# DualMotorCape-v1.net
KiCad netlist of a schematic drawn in EAGLE
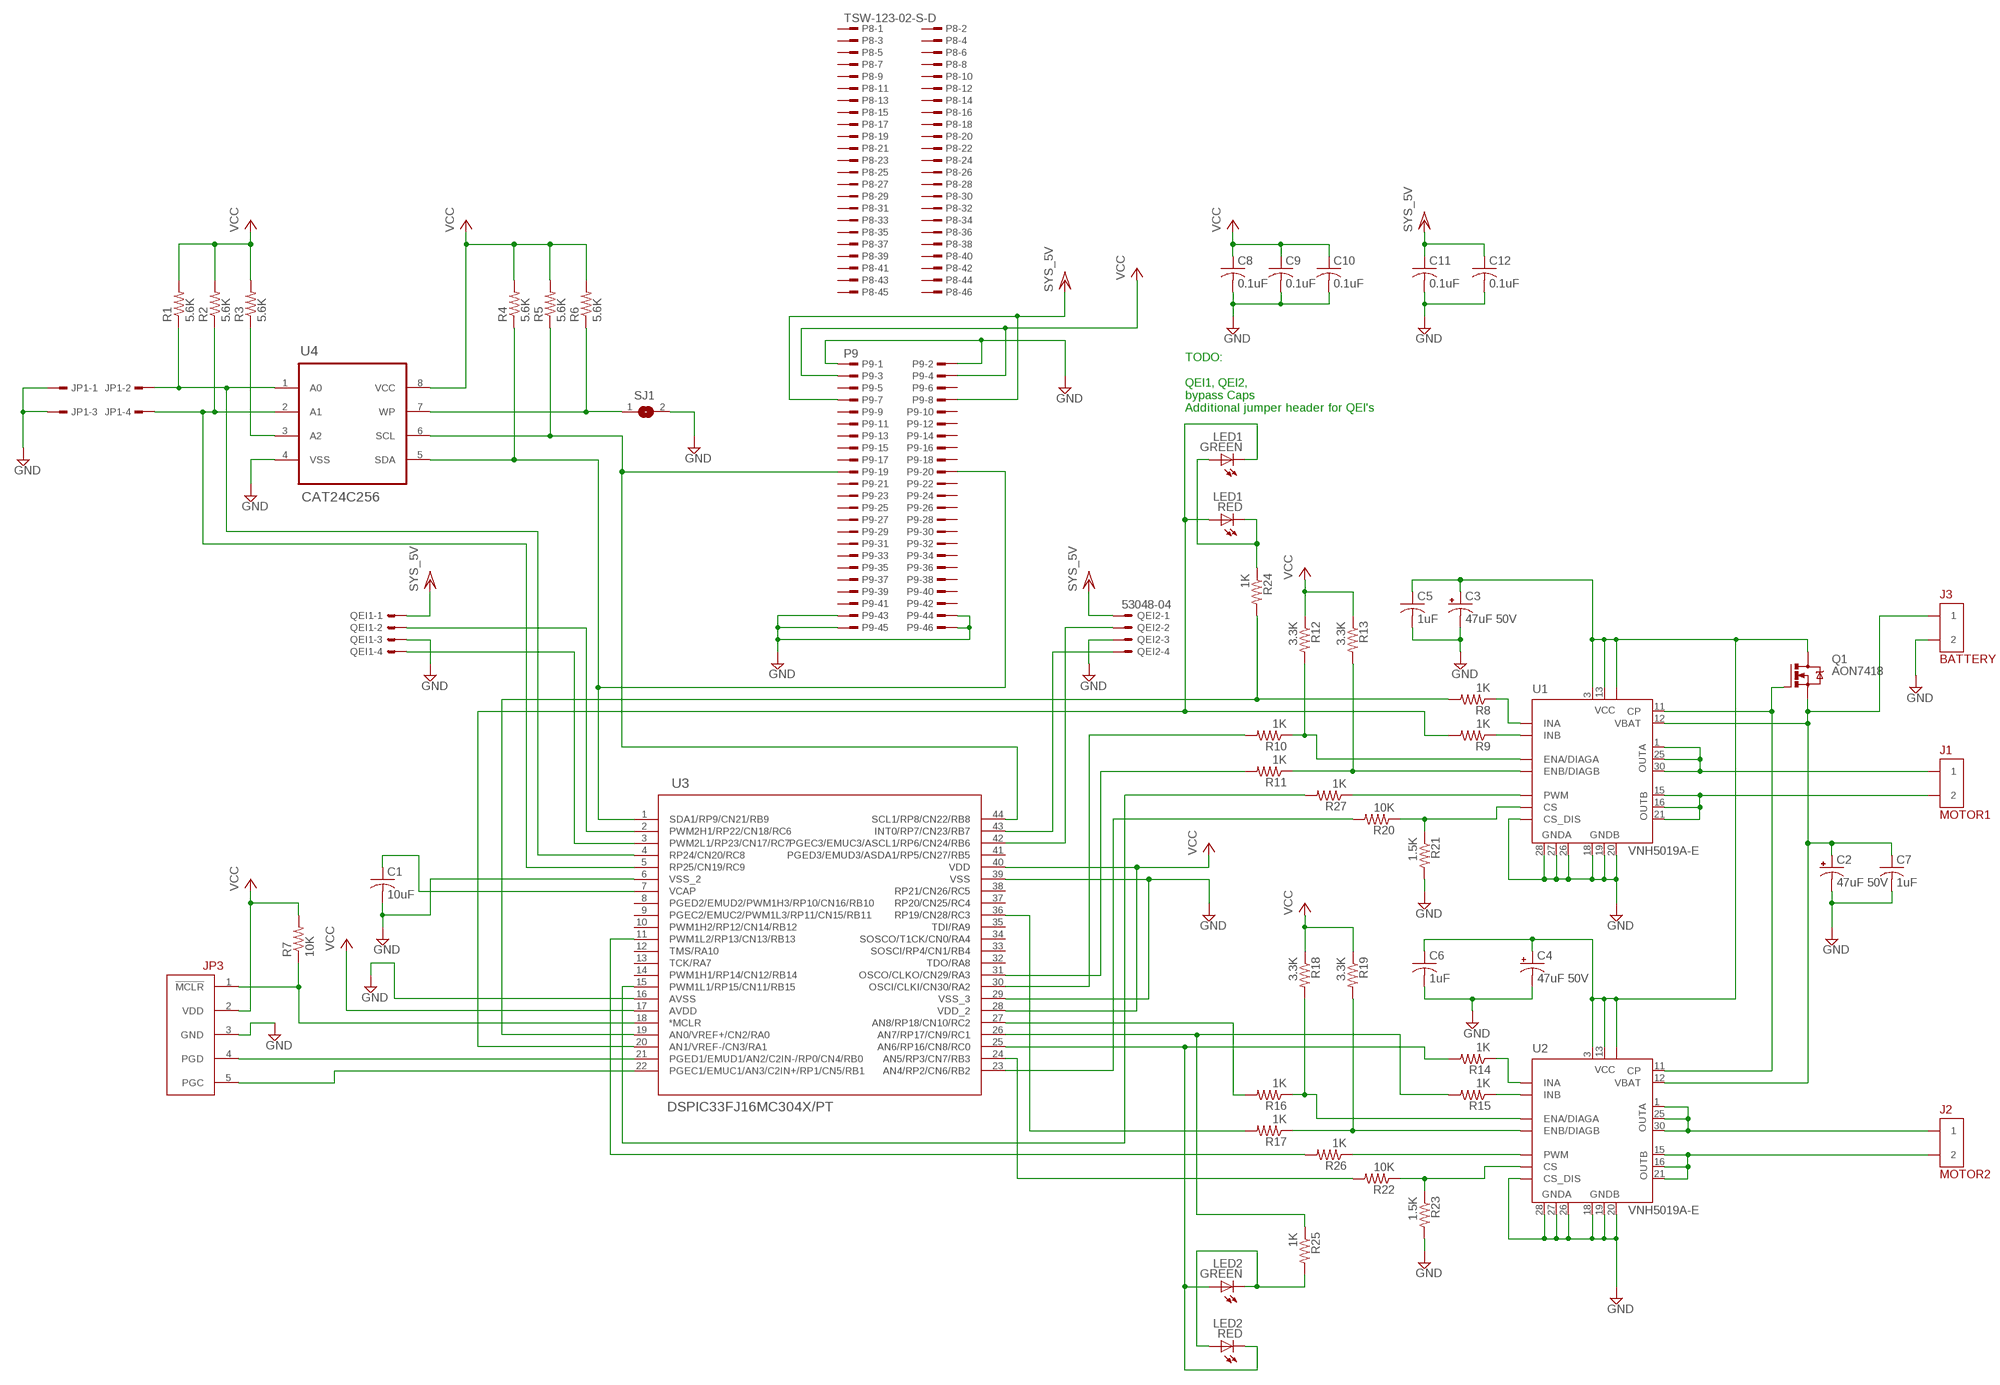
[diagram p0: schematic, sheet 1]

(export (version "E")
  (design (tool "Eeschema 10.0.6"))
  (components
    (comp (ref "C1")
      (value "10uF")
      (footprint "eagle-import:C0805")
      (libsource (lib "eagle-import") (part "C-USC0805"))
    )
    (comp (ref "C2")
      (value "47uF 50V")
      (footprint "eagle-import:UD-6,3X7,7_NICHICON")
      (libsource (lib "eagle-import") (part "CPOL-USUD-6,3X7,7"))
    )
    (comp (ref "C3")
      (value "47uF 50V")
      (footprint "eagle-import:UD-6,3X7,7_NICHICON")
      (libsource (lib "eagle-import") (part "CPOL-USUD-6,3X7,7"))
    )
    (comp (ref "C4")
      (value "47uF 50V")
      (footprint "eagle-import:UD-6,3X7,7_NICHICON")
      (libsource (lib "eagle-import") (part "CPOL-USUD-6,3X7,7"))
    )
    (comp (ref "C5")
      (value "1uF")
      (footprint "eagle-import:C0603")
      (libsource (lib "eagle-import") (part "C-USC0603"))
    )
    (comp (ref "C6")
      (value "1uF")
      (footprint "eagle-import:C0603")
      (libsource (lib "eagle-import") (part "C-USC0603"))
    )
    (comp (ref "C7")
      (value "1uF")
      (footprint "eagle-import:C0603")
      (libsource (lib "eagle-import") (part "C-USC0603"))
    )
    (comp (ref "C8")
      (value "0.1uF")
      (footprint "eagle-import:C0603")
      (libsource (lib "eagle-import") (part "C-USC0603"))
    )
    (comp (ref "C9")
      (value "0.1uF")
      (footprint "eagle-import:C0603")
      (libsource (lib "eagle-import") (part "C-USC0603"))
    )
    (comp (ref "C10")
      (value "0.1uF")
      (footprint "eagle-import:C0603")
      (libsource (lib "eagle-import") (part "C-USC0603"))
    )
    (comp (ref "C11")
      (value "0.1uF")
      (footprint "eagle-import:C0603")
      (libsource (lib "eagle-import") (part "C-USC0603"))
    )
    (comp (ref "C12")
      (value "0.1uF")
      (footprint "eagle-import:C0603")
      (libsource (lib "eagle-import") (part "C-USC0603"))
    )
    (comp (ref "J1")
      (value "MOTOR1")
      (footprint "eagle-import:TERMINAL-BLOCK-2.54MM-2")
      (libsource (lib "eagle-import") (part "TERMINAL-BLOCK-2"))
    )
    (comp (ref "J2")
      (value "MOTOR2")
      (footprint "eagle-import:TERMINAL-BLOCK-2.54MM-2")
      (libsource (lib "eagle-import") (part "TERMINAL-BLOCK-2"))
    )
    (comp (ref "J3")
      (value "BATTERY")
      (footprint "eagle-import:TERMINAL-BLOCK-2.54MM-2")
      (libsource (lib "eagle-import") (part "TERMINAL-BLOCK-2"))
    )
    (comp (ref "JP1")
      (value "TSW-102-02-S-D")
      (footprint "eagle-import:TSW-102-02-S-D")
      (libsource (lib "eagle-import") (part "TSW-102-02-S-D"))
    )
    (comp (ref "JP3")
      (value "ICD2/3-HEADER")
      (footprint "eagle-import:ICD2_3-HEADER")
      (libsource (lib "eagle-import") (part "ICD2/3-HEADER"))
    )
    (comp (ref "LED1")
      (value "KINGBRIGHT-BI-COLOR-LED")
      (footprint "eagle-import:LED-1.6X1.5MM-BI-COLOR")
      (libsource (lib "eagle-import") (part "KINGBRIGHT-BI-COLOR-LED"))
    )
    (comp (ref "LED2")
      (value "KINGBRIGHT-BI-COLOR-LED")
      (footprint "eagle-import:LED-1.6X1.5MM-BI-COLOR")
      (libsource (lib "eagle-import") (part "KINGBRIGHT-BI-COLOR-LED"))
    )
    (comp (ref "P8")
      (value "TSW-123-02-S-D")
      (footprint "eagle-import:TSW-123-02-S-D")
      (libsource (lib "eagle-import") (part "TSW-123-02-S-D"))
    )
    (comp (ref "P9")
      (value "P9")
      (footprint "eagle-import:TSW-123-02-S-D")
      (libsource (lib "eagle-import") (part "TSW-123-02-S-D"))
    )
    (comp (ref "Q1")
      (value "AON7418")
      (footprint "eagle-import:DFN3.3X3.3")
      (libsource (lib "eagle-import") (part "MOSFET-N"))
    )
    (comp (ref "QEI1")
      (value "53048-04")
      (footprint "eagle-import:53048-04")
      (fields (field (name "MF") "MOLEX") (field (name "MPN") "53048-0410"))
      (libsource (lib "eagle-import") (part "53?-04048"))
    )
    (comp (ref "QEI2")
      (value "53048-04")
      (footprint "eagle-import:53048-04")
      (fields (field (name "MF") "MOLEX") (field (name "MPN") "53048-0410"))
      (libsource (lib "eagle-import") (part "53?-04048"))
    )
    (comp (ref "R1")
      (value "5.6K")
      (footprint "eagle-import:R0603")
      (libsource (lib "eagle-import") (part "R-US_R0603"))
    )
    (comp (ref "R2")
      (value "5.6K")
      (footprint "eagle-import:R0603")
      (libsource (lib "eagle-import") (part "R-US_R0603"))
    )
    (comp (ref "R3")
      (value "5.6K")
      (footprint "eagle-import:R0603")
      (libsource (lib "eagle-import") (part "R-US_R0603"))
    )
    (comp (ref "R4")
      (value "5.6K")
      (footprint "eagle-import:R0603")
      (libsource (lib "eagle-import") (part "R-US_R0603"))
    )
    (comp (ref "R5")
      (value "5.6K")
      (footprint "eagle-import:R0603")
      (libsource (lib "eagle-import") (part "R-US_R0603"))
    )
    (comp (ref "R6")
      (value "5.6K")
      (footprint "eagle-import:R0603")
      (libsource (lib "eagle-import") (part "R-US_R0603"))
    )
    (comp (ref "R7")
      (value "10K")
      (footprint "eagle-import:R0603")
      (libsource (lib "eagle-import") (part "R-US_R0603"))
    )
    (comp (ref "R8")
      (value "1K")
      (footprint "eagle-import:R0603")
      (libsource (lib "eagle-import") (part "R-US_R0603"))
    )
    (comp (ref "R9")
      (value "1K")
      (footprint "eagle-import:R0603")
      (libsource (lib "eagle-import") (part "R-US_R0603"))
    )
    (comp (ref "R10")
      (value "1K")
      (footprint "eagle-import:R0603")
      (libsource (lib "eagle-import") (part "R-US_R0603"))
    )
    (comp (ref "R11")
      (value "1K")
      (footprint "eagle-import:R0603")
      (libsource (lib "eagle-import") (part "R-US_R0603"))
    )
    (comp (ref "R12")
      (value "3.3K")
      (footprint "eagle-import:R0603")
      (libsource (lib "eagle-import") (part "R-US_R0603"))
    )
    (comp (ref "R13")
      (value "3.3K")
      (footprint "eagle-import:R0603")
      (libsource (lib "eagle-import") (part "R-US_R0603"))
    )
    (comp (ref "R14")
      (value "1K")
      (footprint "eagle-import:R0603")
      (libsource (lib "eagle-import") (part "R-US_R0603"))
    )
    (comp (ref "R15")
      (value "1K")
      (footprint "eagle-import:R0603")
      (libsource (lib "eagle-import") (part "R-US_R0603"))
    )
    (comp (ref "R16")
      (value "1K")
      (footprint "eagle-import:R0603")
      (libsource (lib "eagle-import") (part "R-US_R0603"))
    )
    (comp (ref "R17")
      (value "1K")
      (footprint "eagle-import:R0603")
      (libsource (lib "eagle-import") (part "R-US_R0603"))
    )
    (comp (ref "R18")
      (value "3.3K")
      (footprint "eagle-import:R0603")
      (libsource (lib "eagle-import") (part "R-US_R0603"))
    )
    (comp (ref "R19")
      (value "3.3K")
      (footprint "eagle-import:R0603")
      (libsource (lib "eagle-import") (part "R-US_R0603"))
    )
    (comp (ref "R20")
      (value "10K")
      (footprint "eagle-import:R0603")
      (libsource (lib "eagle-import") (part "R-US_R0603"))
    )
    (comp (ref "R21")
      (value "1.5K")
      (footprint "eagle-import:R0603")
      (libsource (lib "eagle-import") (part "R-US_R0603"))
    )
    (comp (ref "R22")
      (value "10K")
      (footprint "eagle-import:R0603")
      (libsource (lib "eagle-import") (part "R-US_R0603"))
    )
    (comp (ref "R23")
      (value "1.5K")
      (footprint "eagle-import:R0603")
      (libsource (lib "eagle-import") (part "R-US_R0603"))
    )
    (comp (ref "R24")
      (value "1K")
      (footprint "eagle-import:R0603")
      (libsource (lib "eagle-import") (part "R-US_R0603"))
    )
    (comp (ref "R25")
      (value "1K")
      (footprint "eagle-import:R0603")
      (libsource (lib "eagle-import") (part "R-US_R0603"))
    )
    (comp (ref "R26")
      (value "1K")
      (footprint "eagle-import:R0603")
      (libsource (lib "eagle-import") (part "R-US_R0603"))
    )
    (comp (ref "R27")
      (value "1K")
      (footprint "eagle-import:R0603")
      (libsource (lib "eagle-import") (part "R-US_R0603"))
    )
    (comp (ref "SJ1") (value "SJ") (footprint "eagle-import:SJ") (libsource (lib "eagle-import") (part "SJ")))
    (comp (ref "U1")
      (value "VNH5019A-E")
      (footprint "eagle-import:VNH5019A-E")
      (libsource (lib "eagle-import") (part "VNH5019A-E"))
    )
    (comp (ref "U2")
      (value "VNH5019A-E")
      (footprint "eagle-import:VNH5019A-E")
      (libsource (lib "eagle-import") (part "VNH5019A-E"))
    )
    (comp (ref "U3")
      (value "DSPIC33FJ16MC304X/PT")
      (footprint "eagle-import:TQFP44_MC")
      (libsource (lib "eagle-import") (part "DSPIC33FJ16MC304X/PT"))
    )
    (comp (ref "U4")
      (value "CAT24C256")
      (footprint "eagle-import:SOIC-8")
      (libsource (lib "eagle-import") (part "CAT24C256"))
    )
  )
  (nets
    (net (code "1") (name "GND") (class "Default")
      (node (ref "C1") (pin "2") (pinfunction "2_2") (pintype "passive"))
      (node (ref "C10") (pin "2") (pinfunction "2_2") (pintype "passive"))
      (node (ref "C11") (pin "2") (pinfunction "2_2") (pintype "passive"))
      (node (ref "C12") (pin "2") (pinfunction "2_2") (pintype "passive"))
      (node (ref "C2") (pin "-") (pinfunction "-_-") (pintype "passive"))
      (node (ref "C3") (pin "-") (pinfunction "-_-") (pintype "passive"))
      (node (ref "C4") (pin "-") (pinfunction "-_-") (pintype "passive"))
      (node (ref "C5") (pin "2") (pinfunction "2_2") (pintype "passive"))
      (node (ref "C6") (pin "2") (pinfunction "2_2") (pintype "passive"))
      (node (ref "C7") (pin "2") (pinfunction "2_2") (pintype "passive"))
      (node (ref "C8") (pin "2") (pinfunction "2_2") (pintype "passive"))
      (node (ref "C9") (pin "2") (pinfunction "2_2") (pintype "passive"))
      (node (ref "J3") (pin "2") (pinfunction "2_2") (pintype "passive"))
      (node (ref "JP1") (pin "1") (pinfunction "1_1") (pintype "passive"))
      (node (ref "JP1") (pin "3") (pinfunction "1_3") (pintype "passive"))
      (node (ref "JP3") (pin "3") (pinfunction "GND_3") (pintype "bidirectional"))
      (node (ref "P9") (pin "1") (pinfunction "1_1") (pintype "passive"))
      (node (ref "P9") (pin "2") (pinfunction "1_2") (pintype "passive"))
      (node (ref "P9") (pin "43") (pinfunction "1_43") (pintype "passive"))
      (node (ref "P9") (pin "44") (pinfunction "1_44") (pintype "passive"))
      (node (ref "P9") (pin "45") (pinfunction "1_45") (pintype "passive"))
      (node (ref "P9") (pin "46") (pinfunction "1_46") (pintype "passive"))
      (node (ref "QEI1") (pin "3") (pinfunction "S_3") (pintype "passive"))
      (node (ref "QEI2") (pin "3") (pinfunction "S_3") (pintype "passive"))
      (node (ref "R21") (pin "2") (pinfunction "2_2") (pintype "passive"))
      (node (ref "R23") (pin "2") (pinfunction "2_2") (pintype "passive"))
      (node (ref "SJ1") (pin "2") (pinfunction "2_2") (pintype "passive"))
      (node (ref "U1") (pin "18") (pinfunction "GNDB_18") (pintype "power_in"))
      (node (ref "U1") (pin "19") (pinfunction "GNDB_19") (pintype "power_in"))
      (node (ref "U1") (pin "20") (pinfunction "GNDB_20") (pintype "power_in"))
      (node (ref "U1") (pin "26") (pinfunction "GNDA_26") (pintype "power_in"))
      (node (ref "U1") (pin "27") (pinfunction "GNDA_27") (pintype "power_in"))
      (node (ref "U1") (pin "28") (pinfunction "GNDA_28") (pintype "power_in"))
      (node (ref "U1") (pin "6") (pinfunction "CS_DIS_6") (pintype "input"))
      (node (ref "U2") (pin "18") (pinfunction "GNDB_18") (pintype "power_in"))
      (node (ref "U2") (pin "19") (pinfunction "GNDB_19") (pintype "power_in"))
      (node (ref "U2") (pin "20") (pinfunction "GNDB_20") (pintype "power_in"))
      (node (ref "U2") (pin "26") (pinfunction "GNDA_26") (pintype "power_in"))
      (node (ref "U2") (pin "27") (pinfunction "GNDA_27") (pintype "power_in"))
      (node (ref "U2") (pin "28") (pinfunction "GNDA_28") (pintype "power_in"))
      (node (ref "U2") (pin "6") (pinfunction "CS_DIS_6") (pintype "input"))
      (node (ref "U3") (pin "16") (pinfunction "AVSS_16") (pintype "passive"))
      (node (ref "U3") (pin "29") (pinfunction "VSS_3_29") (pintype "passive"))
      (node (ref "U3") (pin "39") (pinfunction "VSS_39") (pintype "passive"))
      (node (ref "U3") (pin "6") (pinfunction "VSS_2_6") (pintype "passive"))
      (node (ref "U4") (pin "4") (pinfunction "VSS_4") (pintype "power_in"))
    )
    (net (code "2") (name "Net-(C3-Pad+)") (class "Default")
      (node (ref "C3") (pin "+") (pinfunction "+_+") (pintype "passive"))
      (node (ref "C4") (pin "+") (pinfunction "+_+") (pintype "passive"))
      (node (ref "C5") (pin "1") (pinfunction "1_1") (pintype "passive"))
      (node (ref "C6") (pin "1") (pinfunction "1_1") (pintype "passive"))
      (node (ref "Q1") (pin "5") (pinfunction "D_5") (pintype "passive"))
      (node (ref "Q1") (pin "6") (pinfunction "D_6") (pintype "passive"))
      (node (ref "Q1") (pin "7") (pinfunction "D_7") (pintype "passive"))
      (node (ref "Q1") (pin "8") (pinfunction "D_8") (pintype "passive"))
      (node (ref "U1") (pin "13") (pinfunction "VCC_13") (pintype "power_in"))
      (node (ref "U1") (pin "23") (pinfunction "VCC_23") (pintype "power_in"))
      (node (ref "U1") (pin "3") (pinfunction "VCC_3") (pintype "power_in"))
      (node (ref "U2") (pin "13") (pinfunction "VCC_13") (pintype "power_in"))
      (node (ref "U2") (pin "23") (pinfunction "VCC_23") (pintype "power_in"))
      (node (ref "U2") (pin "3") (pinfunction "VCC_3") (pintype "power_in"))
    )
    (net (code "3") (name "Net-(J1-Pad1)") (class "Default")
      (node (ref "J1") (pin "1") (pinfunction "1_1") (pintype "passive"))
      (node (ref "U1") (pin "1") (pinfunction "OUTA_1") (pintype "output"))
      (node (ref "U1") (pin "25") (pinfunction "OUTA_25") (pintype "passive"))
      (node (ref "U1") (pin "30") (pinfunction "OUTA_30") (pintype "passive"))
    )
    (net (code "4") (name "Net-(J1-Pad2)") (class "Default")
      (node (ref "J1") (pin "2") (pinfunction "2_2") (pintype "passive"))
      (node (ref "U1") (pin "15") (pinfunction "OUTB_15") (pintype "output"))
      (node (ref "U1") (pin "16") (pinfunction "OUTB_16") (pintype "passive"))
      (node (ref "U1") (pin "21") (pinfunction "OUTB_21") (pintype "passive"))
    )
    (net (code "5") (name "Net-(J2-Pad1)") (class "Default")
      (node (ref "J2") (pin "1") (pinfunction "1_1") (pintype "passive"))
      (node (ref "U2") (pin "1") (pinfunction "OUTA_1") (pintype "output"))
      (node (ref "U2") (pin "25") (pinfunction "OUTA_25") (pintype "passive"))
      (node (ref "U2") (pin "30") (pinfunction "OUTA_30") (pintype "passive"))
    )
    (net (code "6") (name "Net-(J2-Pad2)") (class "Default")
      (node (ref "J2") (pin "2") (pinfunction "2_2") (pintype "passive"))
      (node (ref "U2") (pin "15") (pinfunction "OUTB_15") (pintype "output"))
      (node (ref "U2") (pin "16") (pinfunction "OUTB_16") (pintype "passive"))
      (node (ref "U2") (pin "21") (pinfunction "OUTB_21") (pintype "passive"))
    )
    (net (code "7") (name "Net-(JP1B-1)") (class "Default")
      (node (ref "JP1") (pin "2") (pinfunction "1_2") (pintype "passive"))
      (node (ref "R1") (pin "1") (pinfunction "1_1") (pintype "passive"))
      (node (ref "U3") (pin "4") (pinfunction "RP24/CN20/RC8_4") (pintype "passive"))
      (node (ref "U4") (pin "1") (pinfunction "A0_1") (pintype "input"))
    )
    (net (code "8") (name "Net-(JP1D-1)") (class "Default")
      (node (ref "JP1") (pin "4") (pinfunction "1_4") (pintype "passive"))
      (node (ref "R2") (pin "1") (pinfunction "1_1") (pintype "passive"))
      (node (ref "U3") (pin "5") (pinfunction "RP25/CN19/RC9_5") (pintype "passive"))
      (node (ref "U4") (pin "2") (pinfunction "A1_2") (pintype "input"))
    )
    (net (code "9") (name "Net-(JP3-PGC)") (class "Default")
      (node (ref "JP3") (pin "5") (pinfunction "PGC_5") (pintype "bidirectional"))
      (node (ref "U3") (pin "22") (pinfunction "PGEC1/EMUC1/AN3/C2IN+/RP1/CN5/RB1_22") (pintype "passive"))
    )
    (net (code "10") (name "Net-(JP3-PGD)") (class "Default")
      (node (ref "JP3") (pin "4") (pinfunction "PGD_4") (pintype "bidirectional"))
      (node (ref "U3") (pin "21") (pinfunction "PGED1/EMUD1/AN2/C2IN-/RP0/CN4/RB0_21") (pintype "passive"))
    )
    (net (code "11") (name "Net-(JP3-~{MCLR})") (class "Default")
      (node (ref "JP3") (pin "1") (pinfunction "~{MCLR}_1") (pintype "bidirectional"))
      (node (ref "R7") (pin "1") (pinfunction "1_1") (pintype "passive"))
      (node (ref "U3") (pin "18") (pinfunction "*MCLR_18") (pintype "passive"))
    )
    (net (code "12") (name "Net-(LED1-Pad2)") (class "Default")
      (node (ref "LED1") (pin "2") (pinfunction "2_2") (pintype "passive"))
      (node (ref "LED1") (pin "3") (pinfunction "3_3") (pintype "passive"))
      (node (ref "R24") (pin "1") (pinfunction "1_1") (pintype "passive"))
    )
    (net (code "13") (name "Net-(LED2-Pad1)") (class "Default")
      (node (ref "LED2") (pin "1") (pinfunction "1_1") (pintype "passive"))
      (node (ref "LED2") (pin "4") (pinfunction "4_4") (pintype "passive"))
      (node (ref "R25") (pin "2") (pinfunction "2_2") (pintype "passive"))
    )
    (net (code "14") (name "Net-(P9K-1)") (class "Default")
      (node (ref "P9") (pin "19") (pinfunction "1_19") (pintype "passive"))
      (node (ref "R5") (pin "1") (pinfunction "1_1") (pintype "passive"))
      (node (ref "U3") (pin "44") (pinfunction "SCL1/RP8/CN22/RB8_44") (pintype "passive"))
      (node (ref "U4") (pin "6") (pinfunction "SCL_6") (pintype "input"))
    )
    (net (code "15") (name "Net-(P9M-1)") (class "Default")
      (node (ref "P9") (pin "20") (pinfunction "1_20") (pintype "passive"))
      (node (ref "R4") (pin "1") (pinfunction "1_1") (pintype "passive"))
      (node (ref "U3") (pin "1") (pinfunction "SDA1/RP9/CN21/RB9_1") (pintype "passive"))
      (node (ref "U4") (pin "5") (pinfunction "SDA_5") (pintype "bidirectional"))
    )
    (net (code "16") (name "Net-(Q1-G)") (class "Default")
      (node (ref "Q1") (pin "4") (pinfunction "G_4") (pintype "passive"))
      (node (ref "U1") (pin "11") (pinfunction "CP_11") (pintype "output"))
      (node (ref "U2") (pin "11") (pinfunction "CP_11") (pintype "output"))
    )
    (net (code "17") (name "Net-(QEI1B-S)") (class "Default")
      (node (ref "QEI1") (pin "2") (pinfunction "S_2") (pintype "passive"))
      (node (ref "U3") (pin "2") (pinfunction "PWM2H1/RP22/CN18/RC6_2") (pintype "passive"))
    )
    (net (code "18") (name "Net-(QEI1D-S)") (class "Default")
      (node (ref "QEI1") (pin "4") (pinfunction "S_4") (pintype "passive"))
      (node (ref "U3") (pin "3") (pinfunction "PWM2L1/RP23/CN17/RC7_3") (pintype "passive"))
    )
    (net (code "19") (name "Net-(QEI2B-S)") (class "Default")
      (node (ref "QEI2") (pin "2") (pinfunction "S_2") (pintype "passive"))
      (node (ref "U3") (pin "42") (pinfunction "PGEC3/EMUC3/ASCL1/RP6/CN24/RB6_42") (pintype "passive"))
    )
    (net (code "20") (name "Net-(QEI2D-S)") (class "Default")
      (node (ref "QEI2") (pin "4") (pinfunction "S_4") (pintype "passive"))
      (node (ref "U3") (pin "43") (pinfunction "INT0/RP7/CN23/RB7_43") (pintype "passive"))
    )
    (net (code "21") (name "Net-(U1-CS)") (class "Default")
      (node (ref "R20") (pin "1") (pinfunction "1_1") (pintype "passive"))
      (node (ref "R21") (pin "1") (pinfunction "1_1") (pintype "passive"))
      (node (ref "U1") (pin "8") (pinfunction "CS_8") (pintype "output"))
    )
    (net (code "22") (name "Net-(U1-ENA{slash}DIAGA)") (class "Default")
      (node (ref "R10") (pin "1") (pinfunction "1_1") (pintype "passive"))
      (node (ref "R12") (pin "2") (pinfunction "2_2") (pintype "passive"))
      (node (ref "U1") (pin "5") (pinfunction "ENA/DIAGA_5") (pintype "open_collector"))
    )
    (net (code "23") (name "Net-(U1-ENB{slash}DIAGB)") (class "Default")
      (node (ref "R11") (pin "1") (pinfunction "1_1") (pintype "passive"))
      (node (ref "R13") (pin "2") (pinfunction "2_2") (pintype "passive"))
      (node (ref "U1") (pin "9") (pinfunction "ENB/DIAGB_9") (pintype "open_collector"))
    )
    (net (code "24") (name "Net-(U1-INA)") (class "Default")
      (node (ref "R8") (pin "1") (pinfunction "1_1") (pintype "passive"))
      (node (ref "U1") (pin "4") (pinfunction "INA_4") (pintype "input"))
    )
    (net (code "25") (name "Net-(U1-INB)") (class "Default")
      (node (ref "R9") (pin "1") (pinfunction "1_1") (pintype "passive"))
      (node (ref "U1") (pin "10") (pinfunction "INB_10") (pintype "input"))
    )
    (net (code "26") (name "Net-(U1-PWM)") (class "Default")
      (node (ref "R27") (pin "1") (pinfunction "1_1") (pintype "passive"))
      (node (ref "U1") (pin "7") (pinfunction "PWM_7") (pintype "input"))
    )
    (net (code "27") (name "Net-(U1-VBAT)") (class "Default")
      (node (ref "C2") (pin "+") (pinfunction "+_+") (pintype "passive"))
      (node (ref "C7") (pin "1") (pinfunction "1_1") (pintype "passive"))
      (node (ref "J3") (pin "1") (pinfunction "1_1") (pintype "passive"))
      (node (ref "Q1") (pin "1") (pinfunction "S_1") (pintype "passive"))
      (node (ref "Q1") (pin "2") (pinfunction "S_2") (pintype "passive"))
      (node (ref "Q1") (pin "3") (pinfunction "S_3") (pintype "passive"))
      (node (ref "U1") (pin "12") (pinfunction "VBAT_12") (pintype "input"))
      (node (ref "U2") (pin "12") (pinfunction "VBAT_12") (pintype "input"))
    )
    (net (code "28") (name "Net-(U2-CS)") (class "Default")
      (node (ref "R22") (pin "1") (pinfunction "1_1") (pintype "passive"))
      (node (ref "R23") (pin "1") (pinfunction "1_1") (pintype "passive"))
      (node (ref "U2") (pin "8") (pinfunction "CS_8") (pintype "output"))
    )
    (net (code "29") (name "Net-(U2-ENA{slash}DIAGA)") (class "Default")
      (node (ref "R16") (pin "1") (pinfunction "1_1") (pintype "passive"))
      (node (ref "R18") (pin "2") (pinfunction "2_2") (pintype "passive"))
      (node (ref "U2") (pin "5") (pinfunction "ENA/DIAGA_5") (pintype "open_collector"))
    )
    (net (code "30") (name "Net-(U2-ENB{slash}DIAGB)") (class "Default")
      (node (ref "R17") (pin "1") (pinfunction "1_1") (pintype "passive"))
      (node (ref "R19") (pin "2") (pinfunction "2_2") (pintype "passive"))
      (node (ref "U2") (pin "9") (pinfunction "ENB/DIAGB_9") (pintype "open_collector"))
    )
    (net (code "31") (name "Net-(U2-INA)") (class "Default")
      (node (ref "R14") (pin "1") (pinfunction "1_1") (pintype "passive"))
      (node (ref "U2") (pin "4") (pinfunction "INA_4") (pintype "input"))
    )
    (net (code "32") (name "Net-(U2-INB)") (class "Default")
      (node (ref "R15") (pin "1") (pinfunction "1_1") (pintype "passive"))
      (node (ref "U2") (pin "10") (pinfunction "INB_10") (pintype "input"))
    )
    (net (code "33") (name "Net-(U2-PWM)") (class "Default")
      (node (ref "R26") (pin "1") (pinfunction "1_1") (pintype "passive"))
      (node (ref "U2") (pin "7") (pinfunction "PWM_7") (pintype "input"))
    )
    (net (code "34") (name "Net-(U3-AN0{slash}VREF+{slash}CN2{slash}RA0)") (class "Default")
      (node (ref "R24") (pin "2") (pinfunction "2_2") (pintype "passive"))
      (node (ref "R8") (pin "2") (pinfunction "2_2") (pintype "passive"))
      (node (ref "U3") (pin "19") (pinfunction "AN0/VREF+/CN2/RA0_19") (pintype "passive"))
    )
    (net (code "35") (name "Net-(U3-AN1{slash}VREF-{slash}CN3{slash}RA1)") (class "Default")
      (node (ref "LED1") (pin "1") (pinfunction "1_1") (pintype "passive"))
      (node (ref "LED1") (pin "4") (pinfunction "4_4") (pintype "passive"))
      (node (ref "R9") (pin "2") (pinfunction "2_2") (pintype "passive"))
      (node (ref "U3") (pin "20") (pinfunction "AN1/VREF-/CN3/RA1_20") (pintype "passive"))
    )
    (net (code "36") (name "Net-(U3-AN4{slash}RP2{slash}CN6{slash}RB2)") (class "Default")
      (node (ref "R20") (pin "2") (pinfunction "2_2") (pintype "passive"))
      (node (ref "U3") (pin "23") (pinfunction "AN4/RP2/CN6/RB2_23") (pintype "passive"))
    )
    (net (code "37") (name "Net-(U3-AN5{slash}RP3{slash}CN7{slash}RB3)") (class "Default")
      (node (ref "R22") (pin "2") (pinfunction "2_2") (pintype "passive"))
      (node (ref "U3") (pin "24") (pinfunction "AN5/RP3/CN7/RB3_24") (pintype "passive"))
    )
    (net (code "38") (name "Net-(U3-AN6{slash}RP16{slash}CN8{slash}RC0)") (class "Default")
      (node (ref "LED2") (pin "2") (pinfunction "2_2") (pintype "passive"))
      (node (ref "LED2") (pin "3") (pinfunction "3_3") (pintype "passive"))
      (node (ref "R14") (pin "2") (pinfunction "2_2") (pintype "passive"))
      (node (ref "U3") (pin "25") (pinfunction "AN6/RP16/CN8/RC0_25") (pintype "passive"))
    )
    (net (code "39") (name "Net-(U3-AN7{slash}RP17{slash}CN9{slash}RC1)") (class "Default")
      (node (ref "R15") (pin "2") (pinfunction "2_2") (pintype "passive"))
      (node (ref "R25") (pin "1") (pinfunction "1_1") (pintype "passive"))
      (node (ref "U3") (pin "26") (pinfunction "AN7/RP17/CN9/RC1_26") (pintype "passive"))
    )
    (net (code "40") (name "Net-(U3-AN8{slash}RP18{slash}CN10{slash}RC2)") (class "Default")
      (node (ref "R16") (pin "2") (pinfunction "2_2") (pintype "passive"))
      (node (ref "U3") (pin "27") (pinfunction "AN8/RP18/CN10/RC2_27") (pintype "passive"))
    )
    (net (code "41") (name "Net-(U3-OSCI{slash}CLKI{slash}CN30{slash}RA2)") (class "Default")
      (node (ref "R10") (pin "2") (pinfunction "2_2") (pintype "passive"))
      (node (ref "U3") (pin "30") (pinfunction "OSCI/CLKI/CN30/RA2_30") (pintype "passive"))
    )
    (net (code "42") (name "Net-(U3-OSCO{slash}CLKO{slash}CN29{slash}RA3)") (class "Default")
      (node (ref "R11") (pin "2") (pinfunction "2_2") (pintype "passive"))
      (node (ref "U3") (pin "31") (pinfunction "OSCO/CLKO/CN29/RA3_31") (pintype "passive"))
    )
    (net (code "43") (name "Net-(U3-PWM1L1{slash}RP15{slash}CN11{slash}RB15)") (class "Default")
      (node (ref "R27") (pin "2") (pinfunction "2_2") (pintype "passive"))
      (node (ref "U3") (pin "15") (pinfunction "PWM1L1/RP15/CN11/RB15_15") (pintype "passive"))
    )
    (net (code "44") (name "Net-(U3-PWM1L2{slash}RP13{slash}CN13{slash}RB13)") (class "Default")
      (node (ref "R26") (pin "2") (pinfunction "2_2") (pintype "passive"))
      (node (ref "U3") (pin "11") (pinfunction "PWM1L2/RP13/CN13/RB13_11") (pintype "passive"))
    )
    (net (code "45") (name "Net-(U3-RP19{slash}CN28{slash}RC3)") (class "Default")
      (node (ref "R17") (pin "2") (pinfunction "2_2") (pintype "passive"))
      (node (ref "U3") (pin "36") (pinfunction "RP19/CN28/RC3_36") (pintype "passive"))
    )
    (net (code "46") (name "Net-(U3-VCAP)") (class "Default")
      (node (ref "C1") (pin "1") (pinfunction "1_1") (pintype "passive"))
      (node (ref "U3") (pin "7") (pinfunction "VCAP_7") (pintype "passive"))
    )
    (net (code "47") (name "Net-(U4-A2)") (class "Default")
      (node (ref "R3") (pin "1") (pinfunction "1_1") (pintype "passive"))
      (node (ref "U4") (pin "3") (pinfunction "A2_3") (pintype "input"))
    )
    (net (code "48") (name "Net-(U4-WP)") (class "Default")
      (node (ref "R6") (pin "1") (pinfunction "1_1") (pintype "passive"))
      (node (ref "SJ1") (pin "1") (pinfunction "1_1") (pintype "passive"))
      (node (ref "U4") (pin "7") (pinfunction "WP_7") (pintype "input"))
    )
    (net (code "49") (name "SYS_5V") (class "Default")
      (node (ref "C11") (pin "1") (pinfunction "1_1") (pintype "passive"))
      (node (ref "C12") (pin "1") (pinfunction "1_1") (pintype "passive"))
      (node (ref "P9") (pin "7") (pinfunction "1_7") (pintype "passive"))
      (node (ref "P9") (pin "8") (pinfunction "1_8") (pintype "passive"))
      (node (ref "QEI1") (pin "1") (pinfunction "S_1") (pintype "passive"))
      (node (ref "QEI2") (pin "1") (pinfunction "S_1") (pintype "passive"))
    )
    (net (code "50") (name "VCC") (class "Default")
      (node (ref "C10") (pin "1") (pinfunction "1_1") (pintype "passive"))
      (node (ref "C8") (pin "1") (pinfunction "1_1") (pintype "passive"))
      (node (ref "C9") (pin "1") (pinfunction "1_1") (pintype "passive"))
      (node (ref "JP3") (pin "2") (pinfunction "VDD_2") (pintype "bidirectional"))
      (node (ref "P9") (pin "3") (pinfunction "1_3") (pintype "passive"))
      (node (ref "P9") (pin "4") (pinfunction "1_4") (pintype "passive"))
      (node (ref "R1") (pin "2") (pinfunction "2_2") (pintype "passive"))
      (node (ref "R12") (pin "1") (pinfunction "1_1") (pintype "passive"))
      (node (ref "R13") (pin "1") (pinfunction "1_1") (pintype "passive"))
      (node (ref "R18") (pin "1") (pinfunction "1_1") (pintype "passive"))
      (node (ref "R19") (pin "1") (pinfunction "1_1") (pintype "passive"))
      (node (ref "R2") (pin "2") (pinfunction "2_2") (pintype "passive"))
      (node (ref "R3") (pin "2") (pinfunction "2_2") (pintype "passive"))
      (node (ref "R4") (pin "2") (pinfunction "2_2") (pintype "passive"))
      (node (ref "R5") (pin "2") (pinfunction "2_2") (pintype "passive"))
      (node (ref "R6") (pin "2") (pinfunction "2_2") (pintype "passive"))
      (node (ref "R7") (pin "2") (pinfunction "2_2") (pintype "passive"))
      (node (ref "U3") (pin "17") (pinfunction "AVDD_17") (pintype "passive"))
      (node (ref "U3") (pin "28") (pinfunction "VDD_2_28") (pintype "passive"))
      (node (ref "U3") (pin "40") (pinfunction "VDD_40") (pintype "passive"))
      (node (ref "U4") (pin "8") (pinfunction "VCC_8") (pintype "power_in"))
    )
    (net (code "51") (name "unconnected-(P8-Pad1)") (class "Default")
      (node (ref "P8") (pin "1") (pinfunction "1_1") (pintype "passive"))
    )
    (net (code "52") (name "unconnected-(P8AA-1-Pad33)") (class "Default")
      (node (ref "P8") (pin "33") (pinfunction "1_33") (pintype "passive"))
    )
    (net (code "53") (name "unconnected-(P8AB-1-Pad34)") (class "Default")
      (node (ref "P8") (pin "34") (pinfunction "1_34") (pintype "passive"))
    )
    (net (code "54") (name "unconnected-(P8AC-1-Pad35)") (class "Default")
      (node (ref "P8") (pin "35") (pinfunction "1_35") (pintype "passive"))
    )
    (net (code "55") (name "unconnected-(P8AD-1-Pad36)") (class "Default")
      (node (ref "P8") (pin "36") (pinfunction "1_36") (pintype "passive"))
    )
    (net (code "56") (name "unconnected-(P8AE-1-Pad37)") (class "Default")
      (node (ref "P8") (pin "37") (pinfunction "1_37") (pintype "passive"))
    )
    (net (code "57") (name "unconnected-(P8AF-1-Pad38)") (class "Default")
      (node (ref "P8") (pin "38") (pinfunction "1_38") (pintype "passive"))
    )
    (net (code "58") (name "unconnected-(P8AG-1-Pad39)") (class "Default")
      (node (ref "P8") (pin "39") (pinfunction "1_39") (pintype "passive"))
    )
    (net (code "59") (name "unconnected-(P8AH-1-Pad4)") (class "Default")
      (node (ref "P8") (pin "4") (pinfunction "1_4") (pintype "passive"))
    )
    (net (code "60") (name "unconnected-(P8AI-1-Pad40)") (class "Default")
      (node (ref "P8") (pin "40") (pinfunction "1_40") (pintype "passive"))
    )
    (net (code "61") (name "unconnected-(P8AJ-1-Pad41)") (class "Default")
      (node (ref "P8") (pin "41") (pinfunction "1_41") (pintype "passive"))
    )
    (net (code "62") (name "unconnected-(P8AK-1-Pad42)") (class "Default")
      (node (ref "P8") (pin "42") (pinfunction "1_42") (pintype "passive"))
    )
    (net (code "63") (name "unconnected-(P8AL-1-Pad43)") (class "Default")
      (node (ref "P8") (pin "43") (pinfunction "1_43") (pintype "passive"))
    )
    (net (code "64") (name "unconnected-(P8AM-1-Pad44)") (class "Default")
      (node (ref "P8") (pin "44") (pinfunction "1_44") (pintype "passive"))
    )
    (net (code "65") (name "unconnected-(P8AN-1-Pad45)") (class "Default")
      (node (ref "P8") (pin "45") (pinfunction "1_45") (pintype "passive"))
    )
    (net (code "66") (name "unconnected-(P8AO-1-Pad46)") (class "Default")
      (node (ref "P8") (pin "46") (pinfunction "1_46") (pintype "passive"))
    )
    (net (code "67") (name "unconnected-(P8AP-1-Pad5)") (class "Default")
      (node (ref "P8") (pin "5") (pinfunction "1_5") (pintype "passive"))
    )
    (net (code "68") (name "unconnected-(P8AQ-1-Pad6)") (class "Default")
      (node (ref "P8") (pin "6") (pinfunction "1_6") (pintype "passive"))
    )
    (net (code "69") (name "unconnected-(P8AR-1-Pad7)") (class "Default")
      (node (ref "P8") (pin "7") (pinfunction "1_7") (pintype "passive"))
    )
    (net (code "70") (name "unconnected-(P8AS-1-Pad8)") (class "Default")
      (node (ref "P8") (pin "8") (pinfunction "1_8") (pintype "passive"))
    )
    (net (code "71") (name "unconnected-(P8AT-1-Pad9)") (class "Default")
      (node (ref "P8") (pin "9") (pinfunction "1_9") (pintype "passive"))
    )
    (net (code "72") (name "unconnected-(P8B-1-Pad10)") (class "Default")
      (node (ref "P8") (pin "10") (pinfunction "1_10") (pintype "passive"))
    )
    (net (code "73") (name "unconnected-(P8C-1-Pad11)") (class "Default")
      (node (ref "P8") (pin "11") (pinfunction "1_11") (pintype "passive"))
    )
    (net (code "74") (name "unconnected-(P8D-1-Pad12)") (class "Default")
      (node (ref "P8") (pin "12") (pinfunction "1_12") (pintype "passive"))
    )
    (net (code "75") (name "unconnected-(P8E-1-Pad13)") (class "Default")
      (node (ref "P8") (pin "13") (pinfunction "1_13") (pintype "passive"))
    )
    (net (code "76") (name "unconnected-(P8F-1-Pad14)") (class "Default")
      (node (ref "P8") (pin "14") (pinfunction "1_14") (pintype "passive"))
    )
    (net (code "77") (name "unconnected-(P8G-1-Pad15)") (class "Default")
      (node (ref "P8") (pin "15") (pinfunction "1_15") (pintype "passive"))
    )
    (net (code "78") (name "unconnected-(P8H-1-Pad16)") (class "Default")
      (node (ref "P8") (pin "16") (pinfunction "1_16") (pintype "passive"))
    )
    (net (code "79") (name "unconnected-(P8I-1-Pad17)") (class "Default")
      (node (ref "P8") (pin "17") (pinfunction "1_17") (pintype "passive"))
    )
    (net (code "80") (name "unconnected-(P8J-1-Pad18)") (class "Default")
      (node (ref "P8") (pin "18") (pinfunction "1_18") (pintype "passive"))
    )
    (net (code "81") (name "unconnected-(P8K-1-Pad19)") (class "Default")
      (node (ref "P8") (pin "19") (pinfunction "1_19") (pintype "passive"))
    )
    (net (code "82") (name "unconnected-(P8L-1-Pad2)") (class "Default")
      (node (ref "P8") (pin "2") (pinfunction "1_2") (pintype "passive"))
    )
    (net (code "83") (name "unconnected-(P8M-1-Pad20)") (class "Default")
      (node (ref "P8") (pin "20") (pinfunction "1_20") (pintype "passive"))
    )
    (net (code "84") (name "unconnected-(P8N-1-Pad21)") (class "Default")
      (node (ref "P8") (pin "21") (pinfunction "1_21") (pintype "passive"))
    )
    (net (code "85") (name "unconnected-(P8O-1-Pad22)") (class "Default")
      (node (ref "P8") (pin "22") (pinfunction "1_22") (pintype "passive"))
    )
    (net (code "86") (name "unconnected-(P8P-1-Pad23)") (class "Default")
      (node (ref "P8") (pin "23") (pinfunction "1_23") (pintype "passive"))
    )
    (net (code "87") (name "unconnected-(P8Q-1-Pad24)") (class "Default")
      (node (ref "P8") (pin "24") (pinfunction "1_24") (pintype "passive"))
    )
    (net (code "88") (name "unconnected-(P8R-1-Pad25)") (class "Default")
      (node (ref "P8") (pin "25") (pinfunction "1_25") (pintype "passive"))
    )
    (net (code "89") (name "unconnected-(P8S-1-Pad26)") (class "Default")
      (node (ref "P8") (pin "26") (pinfunction "1_26") (pintype "passive"))
    )
    (net (code "90") (name "unconnected-(P8T-1-Pad27)") (class "Default")
      (node (ref "P8") (pin "27") (pinfunction "1_27") (pintype "passive"))
    )
    (net (code "91") (name "unconnected-(P8U-1-Pad28)") (class "Default")
      (node (ref "P8") (pin "28") (pinfunction "1_28") (pintype "passive"))
    )
    (net (code "92") (name "unconnected-(P8V-1-Pad29)") (class "Default")
      (node (ref "P8") (pin "29") (pinfunction "1_29") (pintype "passive"))
    )
    (net (code "93") (name "unconnected-(P8W-1-Pad3)") (class "Default")
      (node (ref "P8") (pin "3") (pinfunction "1_3") (pintype "passive"))
    )
    (net (code "94") (name "unconnected-(P8X-1-Pad30)") (class "Default")
      (node (ref "P8") (pin "30") (pinfunction "1_30") (pintype "passive"))
    )
    (net (code "95") (name "unconnected-(P8Y-1-Pad31)") (class "Default")
      (node (ref "P8") (pin "31") (pinfunction "1_31") (pintype "passive"))
    )
    (net (code "96") (name "unconnected-(P8Z-1-Pad32)") (class "Default")
      (node (ref "P8") (pin "32") (pinfunction "1_32") (pintype "passive"))
    )
    (net (code "97") (name "unconnected-(P9AA-1-Pad33)") (class "Default")
      (node (ref "P9") (pin "33") (pinfunction "1_33") (pintype "passive"))
    )
    (net (code "98") (name "unconnected-(P9AB-1-Pad34)") (class "Default")
      (node (ref "P9") (pin "34") (pinfunction "1_34") (pintype "passive"))
    )
    (net (code "99") (name "unconnected-(P9AC-1-Pad35)") (class "Default")
      (node (ref "P9") (pin "35") (pinfunction "1_35") (pintype "passive"))
    )
    (net (code "100") (name "unconnected-(P9AD-1-Pad36)") (class "Default")
      (node (ref "P9") (pin "36") (pinfunction "1_36") (pintype "passive"))
    )
    (net (code "101") (name "unconnected-(P9AE-1-Pad37)") (class "Default")
      (node (ref "P9") (pin "37") (pinfunction "1_37") (pintype "passive"))
    )
    (net (code "102") (name "unconnected-(P9AF-1-Pad38)") (class "Default")
      (node (ref "P9") (pin "38") (pinfunction "1_38") (pintype "passive"))
    )
    (net (code "103") (name "unconnected-(P9AG-1-Pad39)") (class "Default")
      (node (ref "P9") (pin "39") (pinfunction "1_39") (pintype "passive"))
    )
    (net (code "104") (name "unconnected-(P9AI-1-Pad40)") (class "Default")
      (node (ref "P9") (pin "40") (pinfunction "1_40") (pintype "passive"))
    )
    (net (code "105") (name "unconnected-(P9AJ-1-Pad41)") (class "Default")
      (node (ref "P9") (pin "41") (pinfunction "1_41") (pintype "passive"))
    )
    (net (code "106") (name "unconnected-(P9AK-1-Pad42)") (class "Default")
      (node (ref "P9") (pin "42") (pinfunction "1_42") (pintype "passive"))
    )
    (net (code "107") (name "unconnected-(P9AP-1-Pad5)") (class "Default")
      (node (ref "P9") (pin "5") (pinfunction "1_5") (pintype "passive"))
    )
    (net (code "108") (name "unconnected-(P9AQ-1-Pad6)") (class "Default")
      (node (ref "P9") (pin "6") (pinfunction "1_6") (pintype "passive"))
    )
    (net (code "109") (name "unconnected-(P9AT-1-Pad9)") (class "Default")
      (node (ref "P9") (pin "9") (pinfunction "1_9") (pintype "passive"))
    )
    (net (code "110") (name "unconnected-(P9B-1-Pad10)") (class "Default")
      (node (ref "P9") (pin "10") (pinfunction "1_10") (pintype "passive"))
    )
    (net (code "111") (name "unconnected-(P9C-1-Pad11)") (class "Default")
      (node (ref "P9") (pin "11") (pinfunction "1_11") (pintype "passive"))
    )
    (net (code "112") (name "unconnected-(P9D-1-Pad12)") (class "Default")
      (node (ref "P9") (pin "12") (pinfunction "1_12") (pintype "passive"))
    )
    (net (code "113") (name "unconnected-(P9E-1-Pad13)") (class "Default")
      (node (ref "P9") (pin "13") (pinfunction "1_13") (pintype "passive"))
    )
    (net (code "114") (name "unconnected-(P9F-1-Pad14)") (class "Default")
      (node (ref "P9") (pin "14") (pinfunction "1_14") (pintype "passive"))
    )
    (net (code "115") (name "unconnected-(P9G-1-Pad15)") (class "Default")
      (node (ref "P9") (pin "15") (pinfunction "1_15") (pintype "passive"))
    )
    (net (code "116") (name "unconnected-(P9H-1-Pad16)") (class "Default")
      (node (ref "P9") (pin "16") (pinfunction "1_16") (pintype "passive"))
    )
    (net (code "117") (name "unconnected-(P9I-1-Pad17)") (class "Default")
      (node (ref "P9") (pin "17") (pinfunction "1_17") (pintype "passive"))
    )
    (net (code "118") (name "unconnected-(P9J-1-Pad18)") (class "Default")
      (node (ref "P9") (pin "18") (pinfunction "1_18") (pintype "passive"))
    )
    (net (code "119") (name "unconnected-(P9N-1-Pad21)") (class "Default")
      (node (ref "P9") (pin "21") (pinfunction "1_21") (pintype "passive"))
    )
    (net (code "120") (name "unconnected-(P9O-1-Pad22)") (class "Default")
      (node (ref "P9") (pin "22") (pinfunction "1_22") (pintype "passive"))
    )
    (net (code "121") (name "unconnected-(P9P-1-Pad23)") (class "Default")
      (node (ref "P9") (pin "23") (pinfunction "1_23") (pintype "passive"))
    )
    (net (code "122") (name "unconnected-(P9Q-1-Pad24)") (class "Default")
      (node (ref "P9") (pin "24") (pinfunction "1_24") (pintype "passive"))
    )
    (net (code "123") (name "unconnected-(P9R-1-Pad25)") (class "Default")
      (node (ref "P9") (pin "25") (pinfunction "1_25") (pintype "passive"))
    )
    (net (code "124") (name "unconnected-(P9S-1-Pad26)") (class "Default")
      (node (ref "P9") (pin "26") (pinfunction "1_26") (pintype "passive"))
    )
    (net (code "125") (name "unconnected-(P9T-1-Pad27)") (class "Default")
      (node (ref "P9") (pin "27") (pinfunction "1_27") (pintype "passive"))
    )
    (net (code "126") (name "unconnected-(P9U-1-Pad28)") (class "Default")
      (node (ref "P9") (pin "28") (pinfunction "1_28") (pintype "passive"))
    )
    (net (code "127") (name "unconnected-(P9V-1-Pad29)") (class "Default")
      (node (ref "P9") (pin "29") (pinfunction "1_29") (pintype "passive"))
    )
    (net (code "128") (name "unconnected-(P9X-1-Pad30)") (class "Default")
      (node (ref "P9") (pin "30") (pinfunction "1_30") (pintype "passive"))
    )
    (net (code "129") (name "unconnected-(P9Y-1-Pad31)") (class "Default")
      (node (ref "P9") (pin "31") (pinfunction "1_31") (pintype "passive"))
    )
    (net (code "130") (name "unconnected-(P9Z-1-Pad32)") (class "Default")
      (node (ref "P9") (pin "32") (pinfunction "1_32") (pintype "passive"))
    )
    (net (code "131") (name "unconnected-(U3-PGEC2{slash}EMUC2{slash}PWM1L3{slash}RP11{slash}CN15{slash}RB11-Pad9)") (class "Default")
      (node (ref "U3") (pin "9") (pinfunction "PGEC2/EMUC2/PWM1L3/RP11/CN15/RB11_9") (pintype "passive"))
    )
    (net (code "132") (name "unconnected-(U3-PGED2{slash}EMUD2{slash}PWM1H3{slash}RP10{slash}CN16{slash}RB10-Pad8)") (class "Default")
      (node (ref "U3") (pin "8") (pinfunction "PGED2/EMUD2/PWM1H3/RP10/CN16/RB10_8") (pintype "passive"))
    )
    (net (code "133") (name "unconnected-(U3-PGED3{slash}EMUD3{slash}ASDA1{slash}RP5{slash}CN27{slash}RB5-Pad41)") (class "Default")
      (node (ref "U3") (pin "41") (pinfunction "PGED3/EMUD3/ASDA1/RP5/CN27/RB5_41") (pintype "passive"))
    )
    (net (code "134") (name "unconnected-(U3-PWM1H1{slash}RP14{slash}CN12{slash}RB14-Pad14)") (class "Default")
      (node (ref "U3") (pin "14") (pinfunction "PWM1H1/RP14/CN12/RB14_14") (pintype "passive"))
    )
    (net (code "135") (name "unconnected-(U3-PWM1H2{slash}RP12{slash}CN14{slash}RB12-Pad10)") (class "Default")
      (node (ref "U3") (pin "10") (pinfunction "PWM1H2/RP12/CN14/RB12_10") (pintype "passive"))
    )
    (net (code "136") (name "unconnected-(U3-RP20{slash}CN25{slash}RC4-Pad37)") (class "Default")
      (node (ref "U3") (pin "37") (pinfunction "RP20/CN25/RC4_37") (pintype "passive"))
    )
    (net (code "137") (name "unconnected-(U3-RP21{slash}CN26{slash}RC5-Pad38)") (class "Default")
      (node (ref "U3") (pin "38") (pinfunction "RP21/CN26/RC5_38") (pintype "passive"))
    )
    (net (code "138") (name "unconnected-(U3-SOSCI{slash}RP4{slash}CN1{slash}RB4-Pad33)") (class "Default")
      (node (ref "U3") (pin "33") (pinfunction "SOSCI/RP4/CN1/RB4_33") (pintype "passive"))
    )
    (net (code "139") (name "unconnected-(U3-SOSCO{slash}T1CK{slash}CN0{slash}RA4-Pad34)") (class "Default")
      (node (ref "U3") (pin "34") (pinfunction "SOSCO/T1CK/CN0/RA4_34") (pintype "passive"))
    )
    (net (code "140") (name "unconnected-(U3-TCK{slash}RA7-Pad13)") (class "Default")
      (node (ref "U3") (pin "13") (pinfunction "TCK/RA7_13") (pintype "passive"))
    )
    (net (code "141") (name "unconnected-(U3-TDI{slash}RA9-Pad35)") (class "Default")
      (node (ref "U3") (pin "35") (pinfunction "TDI/RA9_35") (pintype "passive"))
    )
    (net (code "142") (name "unconnected-(U3-TDO{slash}RA8-Pad32)") (class "Default")
      (node (ref "U3") (pin "32") (pinfunction "TDO/RA8_32") (pintype "passive"))
    )
    (net (code "143") (name "unconnected-(U3-TMS{slash}RA10-Pad12)") (class "Default")
      (node (ref "U3") (pin "12") (pinfunction "TMS/RA10_12") (pintype "passive"))
    )
  )
)
